# Sheet2.net
KiCad netlist of a schematic drawn in Altium Designer
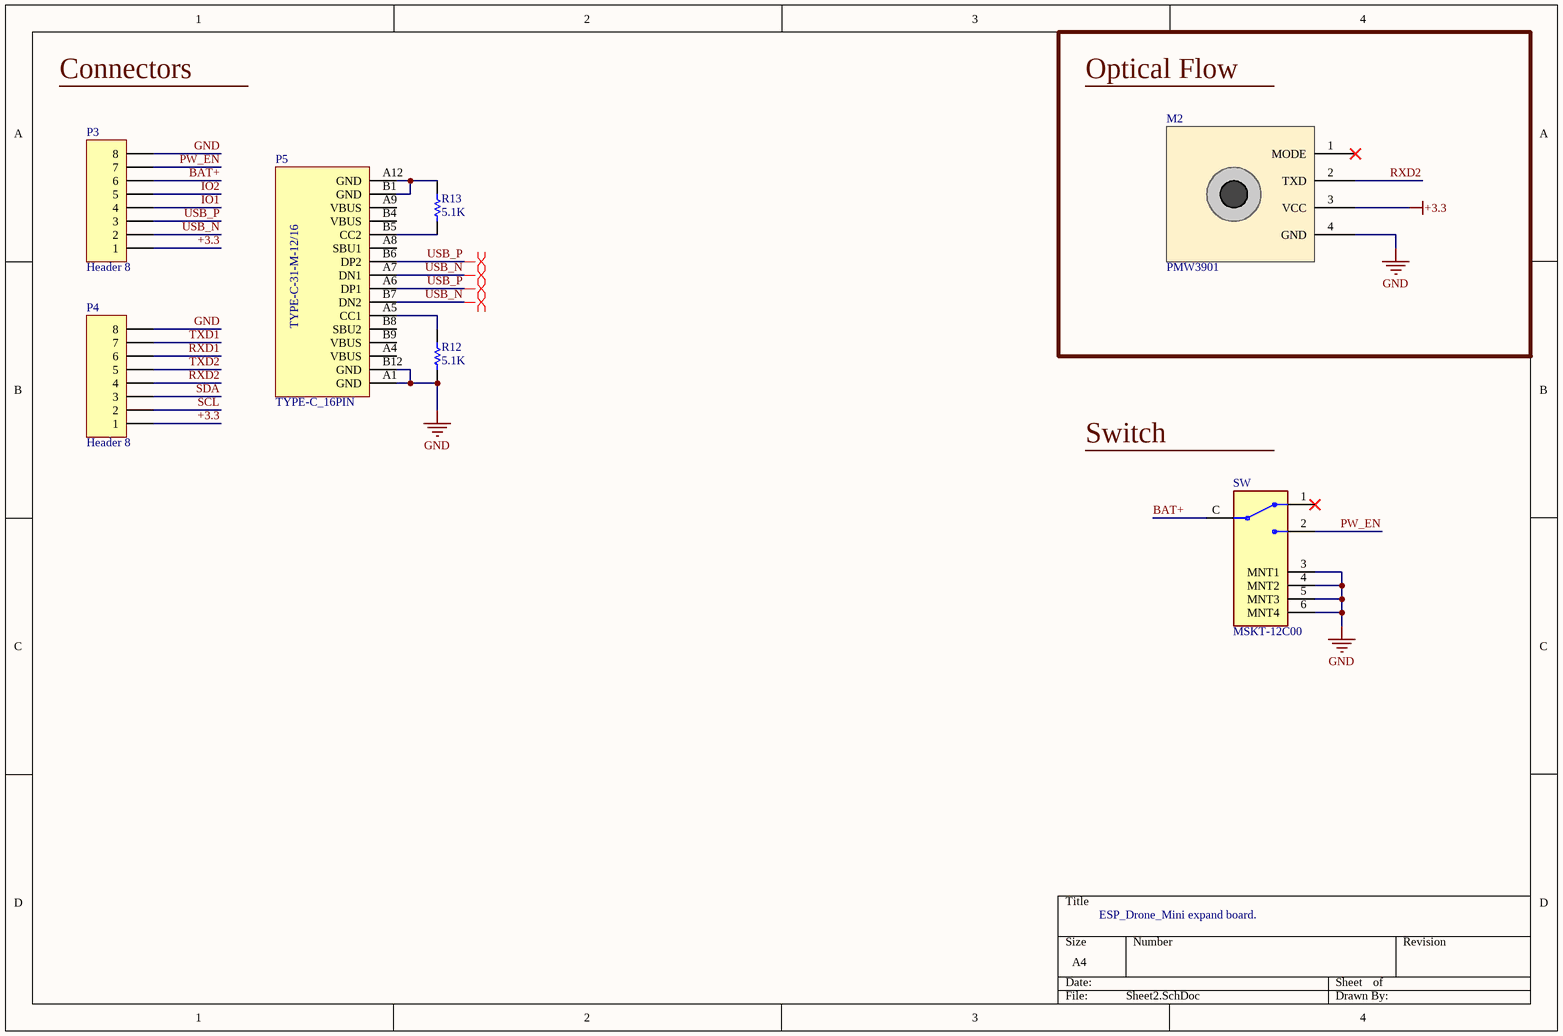
[diagram p0: Sheet2.SchDoc]

(export (version "E")
  (design (tool "Eeschema 10.0.6"))
  (components
    (comp (ref "M2") (value "PMW3901") (libsource (lib "PMW3901") (part "PMW3901")))
    (comp (ref "P3")
      (value "Header 8")
      (footprint "HDR1X8")
      (description "Header, 8-Pin")
      (fields (field (name "PUBLISHER") "Altium Limited"))
      (libsource (lib "Miscellaneous Connectors") (part "Header 8"))
    )
    (comp (ref "P4")
      (value "Header 8")
      (footprint "HDR1X8")
      (description "Header, 8-Pin")
      (fields (field (name "PUBLISHER") "Altium Limited"))
      (libsource (lib "Miscellaneous Connectors") (part "Header 8"))
    )
    (comp (ref "P5")
      (value "TYPE-C_16PIN")
      (footprint "USB-TYPE-C_16PIN")
      (fields (field (name "PUBLISHER") "Altium Limited"))
      (libsource (lib "Type-C-16Pin") (part "TYPE-C_16PIN"))
    )
    (comp (ref "R12")
      (value "5.1K")
      (footprint "RESC2013X60X40LL20T25_A")
      (fields (field (name "TOLERANCE") "0.1%") (field (name "MANUFACTURER") "Panasonic"))
      (libsource (lib "Altium Content Vault") (part "RES-2"))
    )
    (comp (ref "R13")
      (value "5.1K")
      (footprint "RESC2013X60X40LL20T25_A")
      (fields (field (name "TOLERANCE") "0.1%") (field (name "MANUFACTURER") "Panasonic"))
      (libsource (lib "Altium Content Vault") (part "RES-2"))
    )
    (comp (ref "SW")
      (value "MSKT-12C00")
      (footprint "MSKT-12C00")
      (libsource (lib "Switch_and_button") (part "MSKT-12C00"))
    )
  )
  (nets
    (net (code "1") (name "+3.3") (class "Default")
      (node (ref "M2") (pin "3") (pinfunction "VCC_3") (pintype "passive"))
      (node (ref "P3") (pin "1") (pinfunction "1_1") (pintype "passive"))
      (node (ref "P4") (pin "1") (pinfunction "1_1") (pintype "passive"))
    )
    (net (code "2") (name "/BAT+") (class "Default")
      (node (ref "P3") (pin "6") (pinfunction "6_6") (pintype "passive"))
      (node (ref "SW") (pin "C") (pinfunction "C_C") (pintype "passive"))
    )
    (net (code "3") (name "/IO1") (class "Default")
      (node (ref "P3") (pin "4") (pinfunction "4_4") (pintype "passive"))
    )
    (net (code "4") (name "/IO2") (class "Default")
      (node (ref "P3") (pin "5") (pinfunction "5_5") (pintype "passive"))
    )
    (net (code "5") (name "/PW_EN") (class "Default")
      (node (ref "P3") (pin "7") (pinfunction "7_7") (pintype "passive"))
      (node (ref "SW") (pin "2") (pinfunction "2_2") (pintype "passive"))
    )
    (net (code "6") (name "/RXD1") (class "Default")
      (node (ref "P4") (pin "6") (pinfunction "6_6") (pintype "passive"))
    )
    (net (code "7") (name "/RXD2") (class "Default")
      (node (ref "M2") (pin "2") (pinfunction "TXD_2") (pintype "passive"))
      (node (ref "P4") (pin "4") (pinfunction "4_4") (pintype "passive"))
    )
    (net (code "8") (name "/SCL") (class "Default")
      (node (ref "P4") (pin "2") (pinfunction "2_2") (pintype "passive"))
    )
    (net (code "9") (name "/SDA") (class "Default")
      (node (ref "P4") (pin "3") (pinfunction "3_3") (pintype "passive"))
    )
    (net (code "10") (name "/TXD1") (class "Default")
      (node (ref "P4") (pin "7") (pinfunction "7_7") (pintype "passive"))
    )
    (net (code "11") (name "/TXD2") (class "Default")
      (node (ref "P4") (pin "5") (pinfunction "5_5") (pintype "passive"))
    )
    (net (code "12") (name "/USB_N") (class "Default")
      (node (ref "P3") (pin "2") (pinfunction "2_2") (pintype "passive"))
      (node (ref "P5") (pin "A7") (pinfunction "DN1_A7") (pintype "passive"))
      (node (ref "P5") (pin "B7") (pinfunction "DN2_B7") (pintype "passive"))
    )
    (net (code "13") (name "/USB_P") (class "Default")
      (node (ref "P3") (pin "3") (pinfunction "3_3") (pintype "passive"))
      (node (ref "P5") (pin "A6") (pinfunction "DP1_A6") (pintype "passive"))
      (node (ref "P5") (pin "B6") (pinfunction "DP2_B6") (pintype "passive"))
    )
    (net (code "14") (name "GND") (class "Default")
      (node (ref "M2") (pin "4") (pinfunction "GND_4") (pintype "passive"))
      (node (ref "P3") (pin "8") (pinfunction "8_8") (pintype "passive"))
      (node (ref "P4") (pin "8") (pinfunction "8_8") (pintype "passive"))
      (node (ref "P5") (pin "A1") (pinfunction "GND_A1") (pintype "passive"))
      (node (ref "P5") (pin "B12") (pinfunction "GND_B12") (pintype "passive"))
      (node (ref "R12") (pin "1") (pinfunction "1_1") (pintype "passive"))
      (node (ref "SW") (pin "3") (pinfunction "MNT1_3") (pintype "passive"))
      (node (ref "SW") (pin "4") (pinfunction "MNT2_4") (pintype "passive"))
      (node (ref "SW") (pin "5") (pinfunction "MNT3_5") (pintype "passive"))
      (node (ref "SW") (pin "6") (pinfunction "MNT4_6") (pintype "passive"))
    )
    (net (code "15") (name "Net-(P5-CC1)") (class "Default")
      (node (ref "P5") (pin "A5") (pinfunction "CC1_A5") (pintype "passive"))
      (node (ref "R12") (pin "2") (pinfunction "2_2") (pintype "passive"))
    )
    (net (code "16") (name "Net-(P5-CC2)") (class "Default")
      (node (ref "P5") (pin "B5") (pinfunction "CC2_B5") (pintype "passive"))
      (node (ref "R13") (pin "1") (pinfunction "1_1") (pintype "passive"))
    )
    (net (code "17") (name "Net-(P5-GND-PadA12)") (class "Default")
      (node (ref "P5") (pin "A12") (pinfunction "GND_A12") (pintype "passive"))
      (node (ref "P5") (pin "B1") (pinfunction "GND_B1") (pintype "passive"))
      (node (ref "R13") (pin "2") (pinfunction "2_2") (pintype "passive"))
    )
    (net (code "18") (name "unconnected-(M2-MODE-Pad1)") (class "Default")
      (node (ref "M2") (pin "1") (pinfunction "MODE_1") (pintype "passive+no_connect"))
    )
    (net (code "19") (name "unconnected-(P5-SBU1-PadA8)") (class "Default")
      (node (ref "P5") (pin "A8") (pinfunction "SBU1_A8") (pintype "passive"))
    )
    (net (code "20") (name "unconnected-(P5-SBU2-PadB8)") (class "Default")
      (node (ref "P5") (pin "B8") (pinfunction "SBU2_B8") (pintype "passive"))
    )
    (net (code "21") (name "unconnected-(P5-VBUS-PadA4)") (class "Default")
      (node (ref "P5") (pin "A4") (pinfunction "VBUS_A4") (pintype "passive"))
    )
    (net (code "22") (name "unconnected-(P5-VBUS-PadA9)") (class "Default")
      (node (ref "P5") (pin "A9") (pinfunction "VBUS_A9") (pintype "passive"))
    )
    (net (code "23") (name "unconnected-(P5-VBUS-PadB4)") (class "Default")
      (node (ref "P5") (pin "B4") (pinfunction "VBUS_B4") (pintype "passive"))
    )
    (net (code "24") (name "unconnected-(P5-VBUS-PadB9)") (class "Default")
      (node (ref "P5") (pin "B9") (pinfunction "VBUS_B9") (pintype "passive"))
    )
    (net (code "25") (name "unconnected-(SW-Pad1)") (class "Default")
      (node (ref "SW") (pin "1") (pinfunction "1_1") (pintype "passive+no_connect"))
    )
  )
)
